# CANBUSdataLoggerProjectFileV1_2.net
KiCad netlist of a schematic drawn in EasyEDA Pro
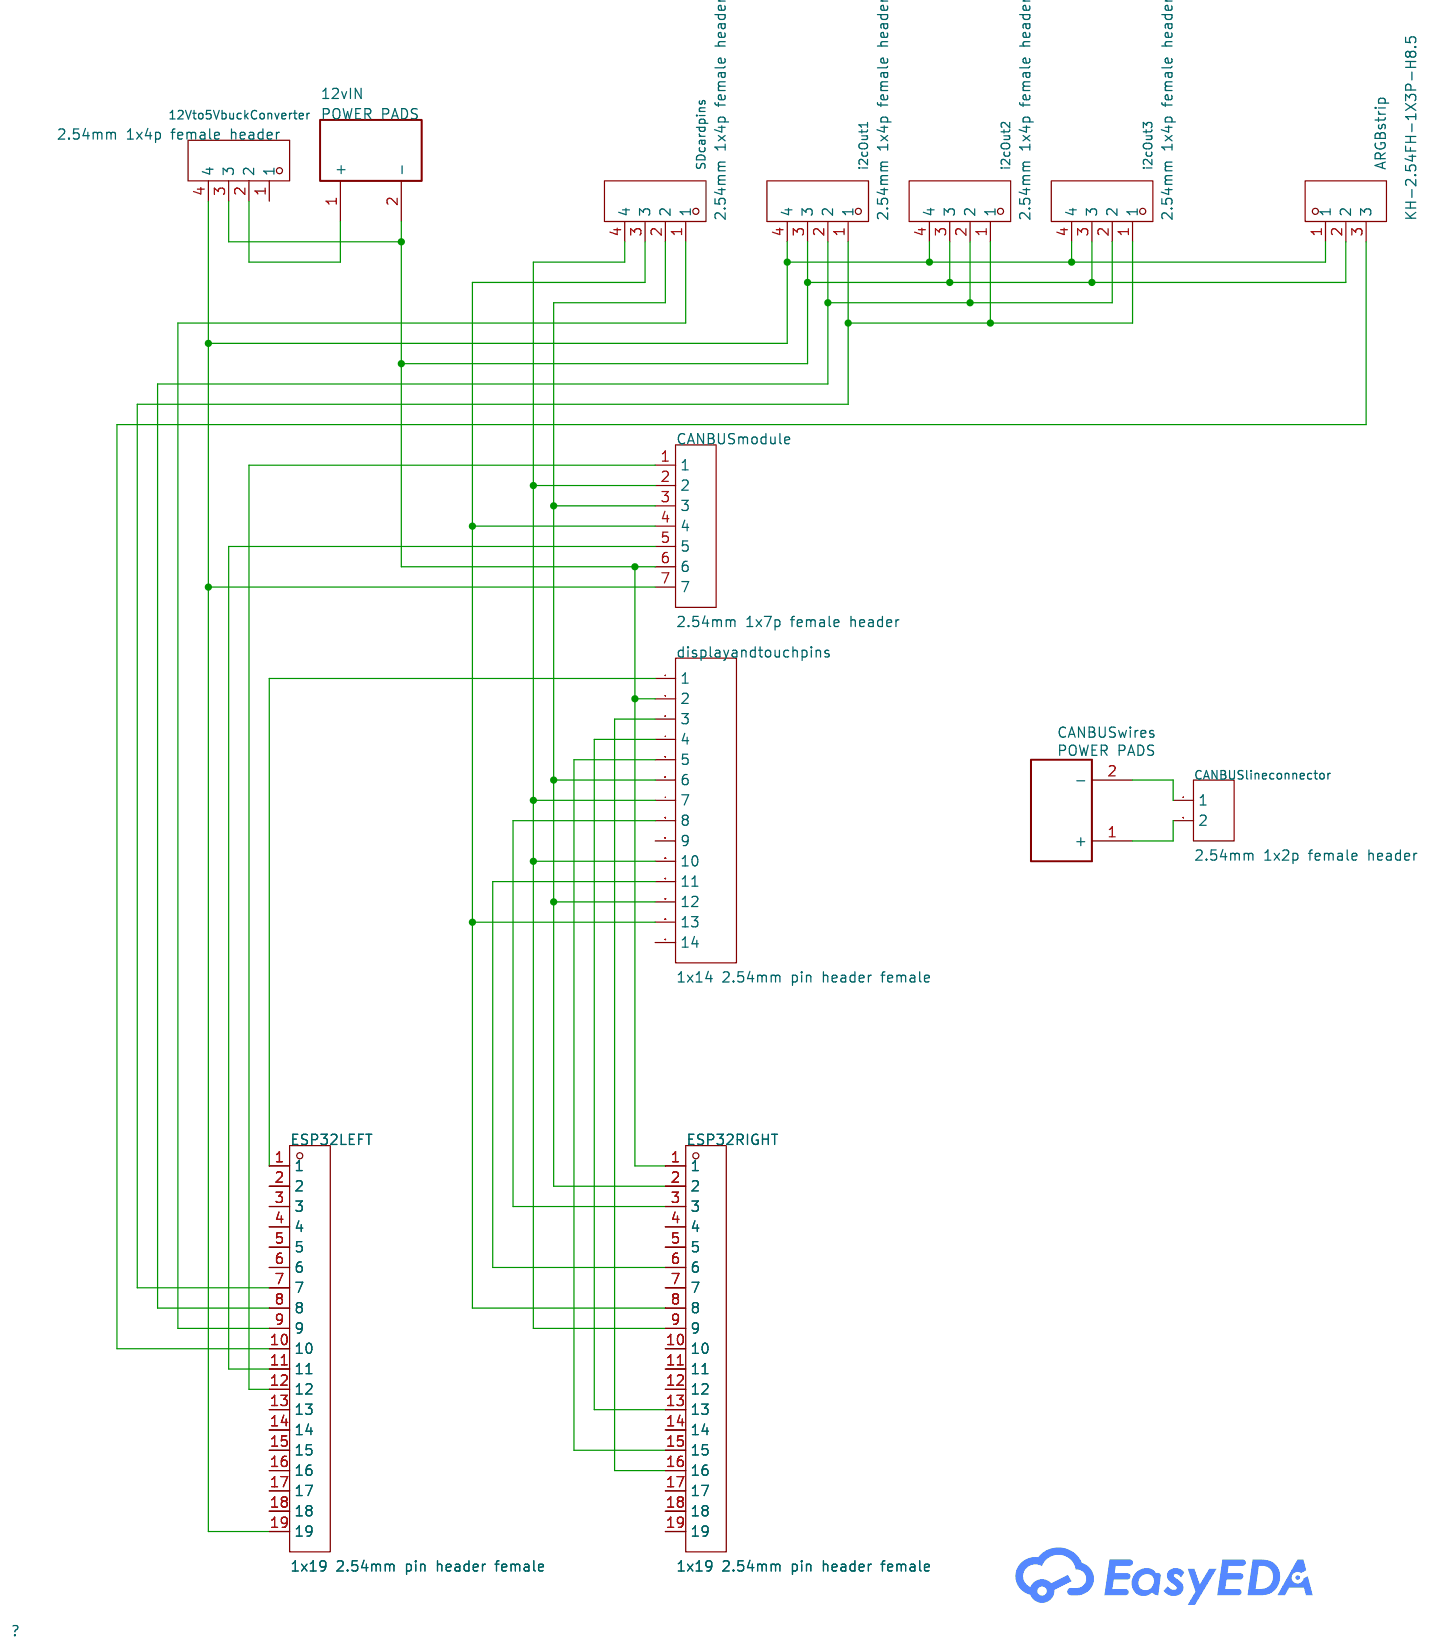
[diagram p0: schematic sheet]

(export (version "E")
  (design (tool "Eeschema 10.0.6"))
  (components
    (comp (ref "12vIN")
      (value "POWER PADS")
      (footprint "easyedapro:POWERPADS")
      (fields (field (name "Contributor") "tomicode"))
      (libsource (lib "easyedapro") (part "POWER PADS"))
    )
    (comp (ref "12Vto5VbuckConverter")
      (value "2.54mm 1x4p female header")
      (footprint "easyedapro:HDR-TH_4P-P2.54-V-F")
      (fields (field (name "Manufacturer") "BOOMELE(博穆精密)"))
      (libsource (lib "easyedapro") (part "2.54-1*4P母"))
    )
    (comp (ref "ARGBstrip")
      (value "KH-2.54FH-1X3P-H8.5")
      (footprint "easyedapro:HDR-TH_3P-P2.54-V-F")
      (fields (field (name "Manufacturer") "kinghelm(金航标)"))
      (libsource (lib "easyedapro") (part "KH-2.54FH-1X3P-H8.5"))
    )
    (comp (ref "CANBUSlineconnector")
      (value "2.54mm 1x2p female header")
      (footprint "easyedapro:HDR-TH_2P-P2.54-V-F")
      (fields (field (name "Manufacturer") "BOOMELE(博穆精密)"))
      (libsource (lib "easyedapro") (part "Header-Female-2.54_1x2"))
    )
    (comp (ref "CANBUSmodule")
      (value "2.54mm 1x7p female header")
      (footprint "easyedapro:HDR-TH_7P-P2.54-V-F")
      (fields (field (name "Manufacturer") "HC(虹成电子)"))
      (libsource (lib "easyedapro") (part "HC-PM254-8.5H-1X7PZ"))
    )
    (comp (ref "CANBUSwires")
      (value "POWER PADS")
      (footprint "easyedapro:POWERPADS")
      (fields (field (name "Contributor") "tomicode"))
      (libsource (lib "easyedapro") (part "POWER PADS"))
    )
    (comp (ref "displayandtouchpins")
      (value "1x14 2.54mm pin header female")
      (footprint "easyedapro:HDR-TH_14P-P2.54-V-F-1")
      (fields (field (name "Manufacturer") "BOOMELE(博穆精密)"))
      (libsource (lib "easyedapro") (part "Female header 2.54-1*14P"))
    )
    (comp (ref "ESP32LEFT")
      (value "1x19 2.54mm pin header female")
      (footprint "easyedapro:HDR-TH_19P-P2.54-V-F")
      (fields (field (name "Manufacturer") "kinghelm(金航标)"))
      (libsource (lib "easyedapro") (part "KH-2.54FH-1X19P-H8.5"))
    )
    (comp (ref "ESP32RIGHT")
      (value "1x19 2.54mm pin header female")
      (footprint "easyedapro:HDR-TH_19P-P2.54-V-F")
      (fields (field (name "Manufacturer") "kinghelm(金航标)"))
      (libsource (lib "easyedapro") (part "KH-2.54FH-1X19P-H8.5"))
    )
    (comp (ref "i2cOut1")
      (value "2.54mm 1x4p female header")
      (footprint "easyedapro:HDR-TH_4P-P2.54-V-F")
      (fields (field (name "Manufacturer") "BOOMELE(博穆精密)"))
      (libsource (lib "easyedapro") (part "2.54-1*4P母"))
    )
    (comp (ref "i2cOut2")
      (value "2.54mm 1x4p female header")
      (footprint "easyedapro:HDR-TH_4P-P2.54-V-F")
      (fields (field (name "Manufacturer") "BOOMELE(博穆精密)"))
      (libsource (lib "easyedapro") (part "2.54-1*4P母"))
    )
    (comp (ref "i2cOut3")
      (value "2.54mm 1x4p female header")
      (footprint "easyedapro:HDR-TH_4P-P2.54-V-F")
      (fields (field (name "Manufacturer") "BOOMELE(博穆精密)"))
      (libsource (lib "easyedapro") (part "2.54-1*4P母"))
    )
    (comp (ref "SDcardpins")
      (value "2.54mm 1x4p female header")
      (footprint "easyedapro:HDR-TH_4P-P2.54-V-F")
      (fields (field (name "Manufacturer") "BOOMELE(博穆精密)"))
      (libsource (lib "easyedapro") (part "2.54-1*4P母"))
    )
  )
  (nets
    (net (code "1") (name "Net-(12Vto5VbuckConverter-Pad4)") (class "Default")
      (node (ref "12Vto5VbuckConverter") (pin "4") (pinfunction "4_4") (pintype "input"))
      (node (ref "ARGBstrip") (pin "1") (pinfunction "1_1") (pintype "unspecified"))
      (node (ref "CANBUSmodule") (pin "7") (pinfunction "7_7") (pintype "unspecified"))
      (node (ref "ESP32LEFT") (pin "19") (pinfunction "19_19") (pintype "unspecified"))
      (node (ref "i2cOut1") (pin "4") (pinfunction "4_4") (pintype "input"))
      (node (ref "i2cOut2") (pin "4") (pinfunction "4_4") (pintype "input"))
      (node (ref "i2cOut3") (pin "4") (pinfunction "4_4") (pintype "input"))
    )
    (net (code "2") (name "Net-(12vIN-+)") (class "Default")
      (node (ref "12Vto5VbuckConverter") (pin "2") (pinfunction "2_2") (pintype "input"))
      (node (ref "12vIN") (pin "1") (pinfunction "+_1") (pintype "unspecified"))
    )
    (net (code "3") (name "Net-(12vIN--)") (class "Default")
      (node (ref "12Vto5VbuckConverter") (pin "3") (pinfunction "3_3") (pintype "input"))
      (node (ref "12vIN") (pin "2") (pinfunction "-_2") (pintype "unspecified"))
      (node (ref "ARGBstrip") (pin "2") (pinfunction "2_2") (pintype "unspecified"))
      (node (ref "CANBUSmodule") (pin "6") (pinfunction "6_6") (pintype "unspecified"))
      (node (ref "ESP32RIGHT") (pin "1") (pinfunction "1_1") (pintype "unspecified"))
      (node (ref "displayandtouchpins") (pin "2") (pinfunction "2_2") (pintype "input"))
      (node (ref "i2cOut1") (pin "3") (pinfunction "3_3") (pintype "input"))
      (node (ref "i2cOut2") (pin "3") (pinfunction "3_3") (pintype "input"))
      (node (ref "i2cOut3") (pin "3") (pinfunction "3_3") (pintype "input"))
    )
    (net (code "4") (name "Net-(ARGBstrip-Pad3)") (class "Default")
      (node (ref "ARGBstrip") (pin "3") (pinfunction "3_3") (pintype "unspecified"))
      (node (ref "ESP32LEFT") (pin "10") (pinfunction "10_10") (pintype "unspecified"))
    )
    (net (code "5") (name "Net-(CANBUSmodule-Pad1)") (class "Default")
      (node (ref "CANBUSmodule") (pin "1") (pinfunction "1_1") (pintype "unspecified"))
      (node (ref "ESP32LEFT") (pin "12") (pinfunction "12_12") (pintype "unspecified"))
    )
    (net (code "6") (name "Net-(CANBUSmodule-Pad2)") (class "Default")
      (node (ref "CANBUSmodule") (pin "2") (pinfunction "2_2") (pintype "unspecified"))
      (node (ref "ESP32RIGHT") (pin "9") (pinfunction "9_9") (pintype "unspecified"))
      (node (ref "SDcardpins") (pin "4") (pinfunction "4_4") (pintype "input"))
      (node (ref "displayandtouchpins") (pin "10") (pinfunction "10_10") (pintype "input"))
      (node (ref "displayandtouchpins") (pin "7") (pinfunction "7_7") (pintype "input"))
    )
    (net (code "7") (name "Net-(CANBUSmodule-Pad3)") (class "Default")
      (node (ref "CANBUSmodule") (pin "3") (pinfunction "3_3") (pintype "unspecified"))
      (node (ref "ESP32RIGHT") (pin "2") (pinfunction "2_2") (pintype "unspecified"))
      (node (ref "SDcardpins") (pin "2") (pinfunction "2_2") (pintype "input"))
      (node (ref "displayandtouchpins") (pin "12") (pinfunction "12_12") (pintype "input"))
      (node (ref "displayandtouchpins") (pin "6") (pinfunction "6_6") (pintype "input"))
    )
    (net (code "8") (name "Net-(CANBUSmodule-Pad4)") (class "Default")
      (node (ref "CANBUSmodule") (pin "4") (pinfunction "4_4") (pintype "unspecified"))
      (node (ref "ESP32RIGHT") (pin "8") (pinfunction "8_8") (pintype "unspecified"))
      (node (ref "SDcardpins") (pin "3") (pinfunction "3_3") (pintype "input"))
      (node (ref "displayandtouchpins") (pin "13") (pinfunction "13_13") (pintype "input"))
    )
    (net (code "9") (name "Net-(CANBUSmodule-Pad5)") (class "Default")
      (node (ref "CANBUSmodule") (pin "5") (pinfunction "5_5") (pintype "unspecified"))
      (node (ref "ESP32LEFT") (pin "11") (pinfunction "11_11") (pintype "unspecified"))
    )
    (net (code "10") (name "Net-(CANBUSwires-+)") (class "Default")
      (node (ref "CANBUSlineconnector") (pin "2") (pinfunction "2_2") (pintype "input"))
      (node (ref "CANBUSwires") (pin "1") (pinfunction "+_1") (pintype "unspecified"))
    )
    (net (code "11") (name "Net-(CANBUSwires--)") (class "Default")
      (node (ref "CANBUSlineconnector") (pin "1") (pinfunction "1_1") (pintype "input"))
      (node (ref "CANBUSwires") (pin "2") (pinfunction "-_2") (pintype "unspecified"))
    )
    (net (code "12") (name "Net-(ESP32LEFT-Pad1)") (class "Default")
      (node (ref "ESP32LEFT") (pin "1") (pinfunction "1_1") (pintype "unspecified"))
      (node (ref "displayandtouchpins") (pin "1") (pinfunction "1_1") (pintype "input"))
    )
    (net (code "13") (name "Net-(ESP32LEFT-Pad7)") (class "Default")
      (node (ref "ESP32LEFT") (pin "7") (pinfunction "7_7") (pintype "unspecified"))
      (node (ref "i2cOut1") (pin "1") (pinfunction "1_1") (pintype "input"))
      (node (ref "i2cOut2") (pin "1") (pinfunction "1_1") (pintype "input"))
      (node (ref "i2cOut3") (pin "1") (pinfunction "1_1") (pintype "input"))
    )
    (net (code "14") (name "Net-(ESP32LEFT-Pad8)") (class "Default")
      (node (ref "ESP32LEFT") (pin "8") (pinfunction "8_8") (pintype "unspecified"))
      (node (ref "i2cOut1") (pin "2") (pinfunction "2_2") (pintype "input"))
      (node (ref "i2cOut2") (pin "2") (pinfunction "2_2") (pintype "input"))
      (node (ref "i2cOut3") (pin "2") (pinfunction "2_2") (pintype "input"))
    )
    (net (code "15") (name "Net-(ESP32LEFT-Pad9)") (class "Default")
      (node (ref "ESP32LEFT") (pin "9") (pinfunction "9_9") (pintype "unspecified"))
      (node (ref "SDcardpins") (pin "1") (pinfunction "1_1") (pintype "input"))
    )
    (net (code "16") (name "Net-(ESP32RIGHT-Pad3)") (class "Default")
      (node (ref "ESP32RIGHT") (pin "3") (pinfunction "3_3") (pintype "unspecified"))
      (node (ref "displayandtouchpins") (pin "8") (pinfunction "8_8") (pintype "input"))
    )
    (net (code "17") (name "Net-(ESP32RIGHT-Pad6)") (class "Default")
      (node (ref "ESP32RIGHT") (pin "6") (pinfunction "6_6") (pintype "unspecified"))
      (node (ref "displayandtouchpins") (pin "11") (pinfunction "11_11") (pintype "input"))
    )
    (net (code "18") (name "Net-(ESP32RIGHT-Pad13)") (class "Default")
      (node (ref "ESP32RIGHT") (pin "13") (pinfunction "13_13") (pintype "unspecified"))
      (node (ref "displayandtouchpins") (pin "4") (pinfunction "4_4") (pintype "input"))
    )
    (net (code "19") (name "Net-(ESP32RIGHT-Pad15)") (class "Default")
      (node (ref "ESP32RIGHT") (pin "15") (pinfunction "15_15") (pintype "unspecified"))
      (node (ref "displayandtouchpins") (pin "5") (pinfunction "5_5") (pintype "input"))
    )
    (net (code "20") (name "Net-(ESP32RIGHT-Pad16)") (class "Default")
      (node (ref "ESP32RIGHT") (pin "16") (pinfunction "16_16") (pintype "unspecified"))
      (node (ref "displayandtouchpins") (pin "3") (pinfunction "3_3") (pintype "input"))
    )
    (net (code "21") (name "unconnected-(12Vto5VbuckConverter-Pad1)") (class "Default")
      (node (ref "12Vto5VbuckConverter") (pin "1") (pinfunction "1_1") (pintype "input"))
    )
    (net (code "22") (name "unconnected-(ESP32LEFT-Pad2)") (class "Default")
      (node (ref "ESP32LEFT") (pin "2") (pinfunction "2_2") (pintype "unspecified"))
    )
    (net (code "23") (name "unconnected-(ESP32LEFT-Pad3)") (class "Default")
      (node (ref "ESP32LEFT") (pin "3") (pinfunction "3_3") (pintype "unspecified"))
    )
    (net (code "24") (name "unconnected-(ESP32LEFT-Pad4)") (class "Default")
      (node (ref "ESP32LEFT") (pin "4") (pinfunction "4_4") (pintype "unspecified"))
    )
    (net (code "25") (name "unconnected-(ESP32LEFT-Pad5)") (class "Default")
      (node (ref "ESP32LEFT") (pin "5") (pinfunction "5_5") (pintype "unspecified"))
    )
    (net (code "26") (name "unconnected-(ESP32LEFT-Pad6)") (class "Default")
      (node (ref "ESP32LEFT") (pin "6") (pinfunction "6_6") (pintype "unspecified"))
    )
    (net (code "27") (name "unconnected-(ESP32LEFT-Pad13)") (class "Default")
      (node (ref "ESP32LEFT") (pin "13") (pinfunction "13_13") (pintype "unspecified"))
    )
    (net (code "28") (name "unconnected-(ESP32LEFT-Pad14)") (class "Default")
      (node (ref "ESP32LEFT") (pin "14") (pinfunction "14_14") (pintype "unspecified"))
    )
    (net (code "29") (name "unconnected-(ESP32LEFT-Pad15)") (class "Default")
      (node (ref "ESP32LEFT") (pin "15") (pinfunction "15_15") (pintype "unspecified"))
    )
    (net (code "30") (name "unconnected-(ESP32LEFT-Pad16)") (class "Default")
      (node (ref "ESP32LEFT") (pin "16") (pinfunction "16_16") (pintype "unspecified"))
    )
    (net (code "31") (name "unconnected-(ESP32LEFT-Pad17)") (class "Default")
      (node (ref "ESP32LEFT") (pin "17") (pinfunction "17_17") (pintype "unspecified"))
    )
    (net (code "32") (name "unconnected-(ESP32LEFT-Pad18)") (class "Default")
      (node (ref "ESP32LEFT") (pin "18") (pinfunction "18_18") (pintype "unspecified"))
    )
    (net (code "33") (name "unconnected-(ESP32RIGHT-Pad4)") (class "Default")
      (node (ref "ESP32RIGHT") (pin "4") (pinfunction "4_4") (pintype "unspecified"))
    )
    (net (code "34") (name "unconnected-(ESP32RIGHT-Pad5)") (class "Default")
      (node (ref "ESP32RIGHT") (pin "5") (pinfunction "5_5") (pintype "unspecified"))
    )
    (net (code "35") (name "unconnected-(ESP32RIGHT-Pad7)") (class "Default")
      (node (ref "ESP32RIGHT") (pin "7") (pinfunction "7_7") (pintype "unspecified"))
    )
    (net (code "36") (name "unconnected-(ESP32RIGHT-Pad10)") (class "Default")
      (node (ref "ESP32RIGHT") (pin "10") (pinfunction "10_10") (pintype "unspecified"))
    )
    (net (code "37") (name "unconnected-(ESP32RIGHT-Pad11)") (class "Default")
      (node (ref "ESP32RIGHT") (pin "11") (pinfunction "11_11") (pintype "unspecified"))
    )
    (net (code "38") (name "unconnected-(ESP32RIGHT-Pad12)") (class "Default")
      (node (ref "ESP32RIGHT") (pin "12") (pinfunction "12_12") (pintype "unspecified"))
    )
    (net (code "39") (name "unconnected-(ESP32RIGHT-Pad14)") (class "Default")
      (node (ref "ESP32RIGHT") (pin "14") (pinfunction "14_14") (pintype "unspecified"))
    )
    (net (code "40") (name "unconnected-(ESP32RIGHT-Pad17)") (class "Default")
      (node (ref "ESP32RIGHT") (pin "17") (pinfunction "17_17") (pintype "unspecified"))
    )
    (net (code "41") (name "unconnected-(ESP32RIGHT-Pad18)") (class "Default")
      (node (ref "ESP32RIGHT") (pin "18") (pinfunction "18_18") (pintype "unspecified"))
    )
    (net (code "42") (name "unconnected-(ESP32RIGHT-Pad19)") (class "Default")
      (node (ref "ESP32RIGHT") (pin "19") (pinfunction "19_19") (pintype "unspecified"))
    )
    (net (code "43") (name "unconnected-(displayandtouchpins-Pad9)") (class "Default")
      (node (ref "displayandtouchpins") (pin "9") (pinfunction "9_9") (pintype "input"))
    )
    (net (code "44") (name "unconnected-(displayandtouchpins-Pad14)") (class "Default")
      (node (ref "displayandtouchpins") (pin "14") (pinfunction "14_14") (pintype "input"))
    )
  )
)
